# powersystem.net
KiCad netlist of a schematic drawn in EAGLE
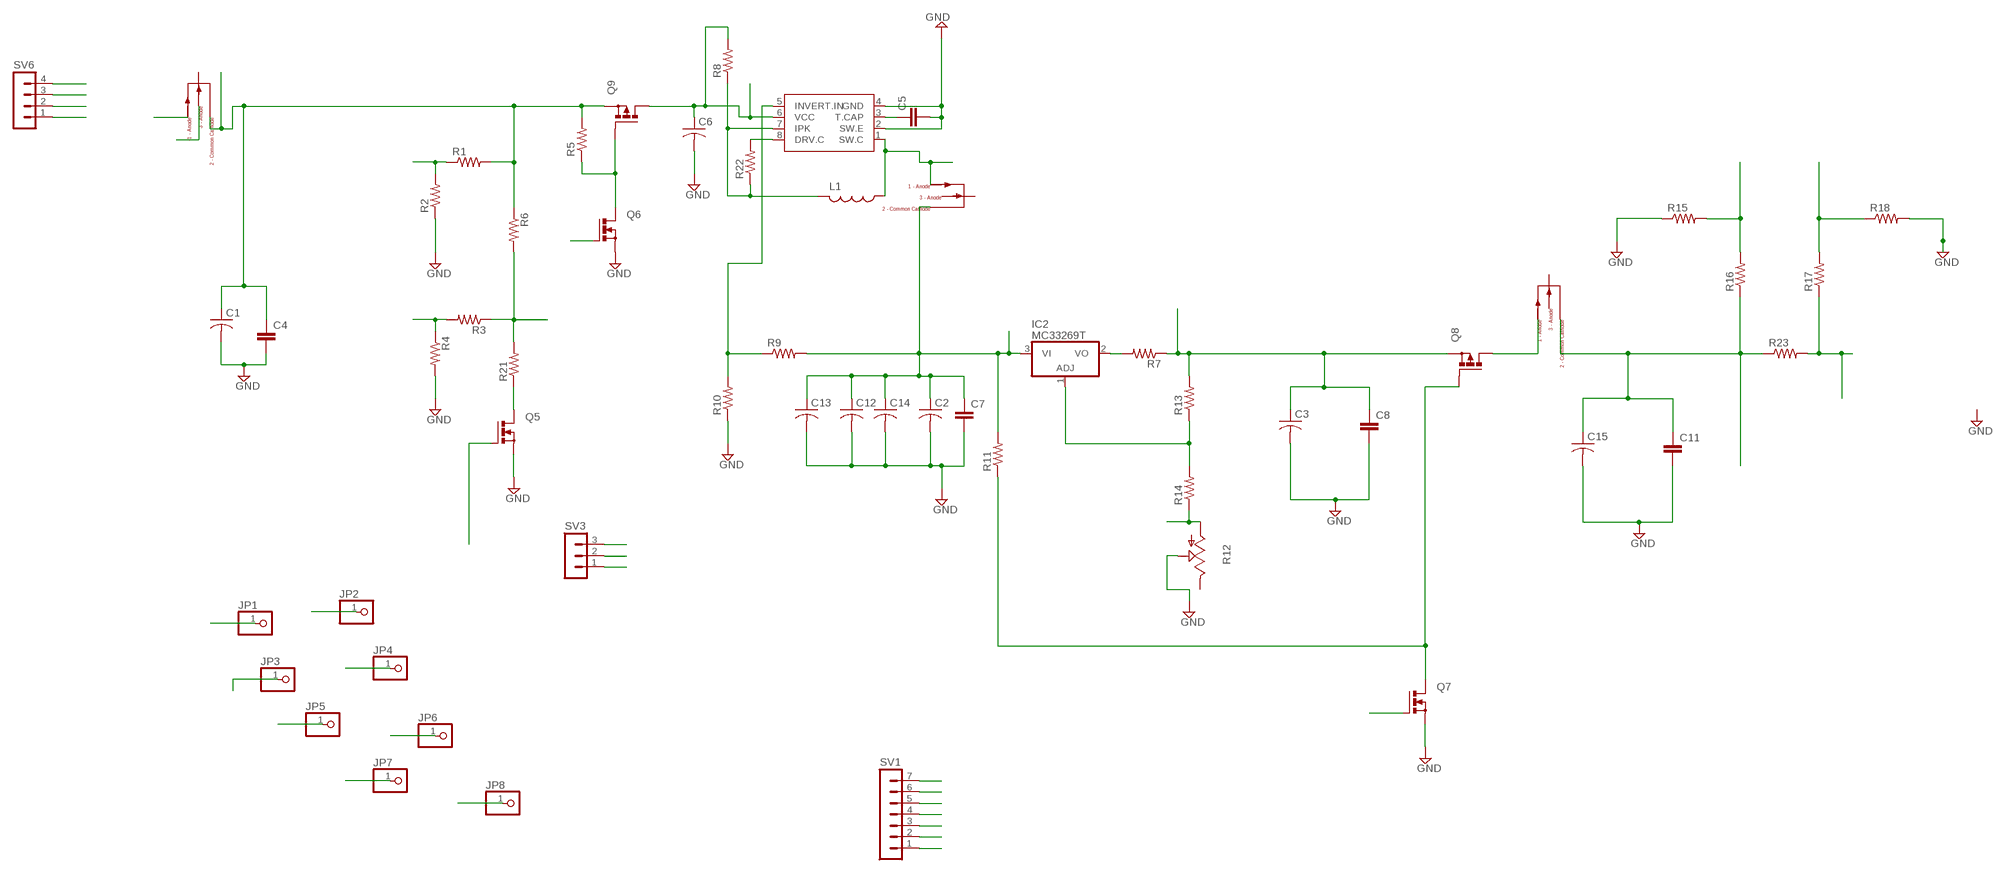
[diagram p0: schematic, sheet 1]

(export (version "E")
  (design (tool "Eeschema 10.0.6"))
  (components
    (comp (ref "C1")
      (value "C-US025-024X044")
      (footprint "eagle-import:C025-024X044")
      (libsource (lib "eagle-import") (part "C-US025-024X044"))
    )
    (comp (ref "C2")
      (value "C-US025-024X044")
      (footprint "eagle-import:C025-024X044")
      (libsource (lib "eagle-import") (part "C-US025-024X044"))
    )
    (comp (ref "C3")
      (value "C-US025-024X044")
      (footprint "eagle-import:C025-024X044")
      (libsource (lib "eagle-import") (part "C-US025-024X044"))
    )
    (comp (ref "C4")
      (value "C2.5/2")
      (footprint "eagle-import:C2.5-2")
      (libsource (lib "eagle-import") (part "C2.5/2"))
    )
    (comp (ref "C5")
      (value "C2.5/2")
      (footprint "eagle-import:C2.5-2")
      (libsource (lib "eagle-import") (part "C2.5/2"))
    )
    (comp (ref "C6")
      (value "C-US025-024X044")
      (footprint "eagle-import:C025-024X044")
      (libsource (lib "eagle-import") (part "C-US025-024X044"))
    )
    (comp (ref "C7")
      (value "C2.5/2")
      (footprint "eagle-import:C2.5-2")
      (libsource (lib "eagle-import") (part "C2.5/2"))
    )
    (comp (ref "C8")
      (value "C2.5/2")
      (footprint "eagle-import:C2.5-2")
      (libsource (lib "eagle-import") (part "C2.5/2"))
    )
    (comp (ref "C11")
      (value "C2.5/2")
      (footprint "eagle-import:C2.5-2")
      (libsource (lib "eagle-import") (part "C2.5/2"))
    )
    (comp (ref "C12")
      (value "C-US025-024X044")
      (footprint "eagle-import:C025-024X044")
      (libsource (lib "eagle-import") (part "C-US025-024X044"))
    )
    (comp (ref "C13")
      (value "C-US025-024X044")
      (footprint "eagle-import:C025-024X044")
      (libsource (lib "eagle-import") (part "C-US025-024X044"))
    )
    (comp (ref "C14")
      (value "C-US025-024X044")
      (footprint "eagle-import:C025-024X044")
      (libsource (lib "eagle-import") (part "C-US025-024X044"))
    )
    (comp (ref "C15")
      (value "C-US025-024X044")
      (footprint "eagle-import:C025-024X044")
      (libsource (lib "eagle-import") (part "C-US025-024X044"))
    )
    (comp (ref "IC2")
      (value "MC33269T")
      (footprint "eagle-import:TO220V")
      (libsource (lib "eagle-import") (part "MC33269?T"))
    )
    (comp (ref "JP1")
      (value "PINHD-1X1")
      (footprint "eagle-import:1X01")
      (libsource (lib "eagle-import") (part "PINHD-1X1"))
    )
    (comp (ref "JP2")
      (value "PINHD-1X1")
      (footprint "eagle-import:1X01")
      (libsource (lib "eagle-import") (part "PINHD-1X1"))
    )
    (comp (ref "JP3")
      (value "PINHD-1X1")
      (footprint "eagle-import:1X01")
      (libsource (lib "eagle-import") (part "PINHD-1X1"))
    )
    (comp (ref "JP4")
      (value "PINHD-1X1")
      (footprint "eagle-import:1X01")
      (libsource (lib "eagle-import") (part "PINHD-1X1"))
    )
    (comp (ref "JP5")
      (value "PINHD-1X1")
      (footprint "eagle-import:1X01")
      (libsource (lib "eagle-import") (part "PINHD-1X1"))
    )
    (comp (ref "JP6")
      (value "PINHD-1X1")
      (footprint "eagle-import:1X01")
      (libsource (lib "eagle-import") (part "PINHD-1X1"))
    )
    (comp (ref "JP7")
      (value "PINHD-1X1")
      (footprint "eagle-import:1X01")
      (libsource (lib "eagle-import") (part "PINHD-1X1"))
    )
    (comp (ref "JP8")
      (value "PINHD-1X1")
      (footprint "eagle-import:1X01")
      (libsource (lib "eagle-import") (part "PINHD-1X1"))
    )
    (comp (ref "L1")
      (value "L-US0204/5")
      (footprint "eagle-import:0204_5")
      (libsource (lib "eagle-import") (part "L-US0204/5"))
    )
    (comp (ref "Q1")
      (value "PMOSFET_N")
      (footprint "eagle-import:TO220BV")
      (libsource (lib "eagle-import") (part "PMOSFET_N"))
    )
    (comp (ref "Q2")
      (value "PMOSFET_N")
      (footprint "eagle-import:TO220BV")
      (libsource (lib "eagle-import") (part "PMOSFET_N"))
    )
    (comp (ref "Q3")
      (value "PMOSFET_N")
      (footprint "eagle-import:TO220BV")
      (libsource (lib "eagle-import") (part "PMOSFET_N"))
    )
    (comp (ref "Q4")
      (value "UCC38050")
      (footprint "eagle-import:DIP-8")
      (libsource (lib "eagle-import") (part "UCC38050"))
    )
    (comp (ref "Q5")
      (value "PMOSFET_NTO220BV")
      (footprint "eagle-import:TO220BV")
      (libsource (lib "eagle-import") (part "transistor-power_400_PMOSFET_NTO220BV"))
    )
    (comp (ref "Q6")
      (value "PMOSFET_NTO220BV")
      (footprint "eagle-import:TO220BV")
      (libsource (lib "eagle-import") (part "transistor-power_400_PMOSFET_NTO220BV"))
    )
    (comp (ref "Q7")
      (value "PMOSFET_NTO220BV")
      (footprint "eagle-import:TO220BV")
      (libsource (lib "eagle-import") (part "transistor-power_400_PMOSFET_NTO220BV"))
    )
    (comp (ref "Q8")
      (value "PMOSFET_PTO220BV")
      (footprint "eagle-import:TO220BV")
      (libsource (lib "eagle-import") (part "PMOSFET_PTO220BV"))
    )
    (comp (ref "Q9")
      (value "PMOSFET_PTO220BV")
      (footprint "eagle-import:TO220BV")
      (libsource (lib "eagle-import") (part "PMOSFET_PTO220BV"))
    )
    (comp (ref "R1")
      (value "R-US_0204/7")
      (footprint "eagle-import:0204_7")
      (libsource (lib "eagle-import") (part "resistor_348_R-US_0204/7"))
    )
    (comp (ref "R2")
      (value "R-US_0204/7")
      (footprint "eagle-import:0204_7")
      (libsource (lib "eagle-import") (part "resistor_348_R-US_0204/7"))
    )
    (comp (ref "R3")
      (value "R-US_0204/7")
      (footprint "eagle-import:0204_7")
      (libsource (lib "eagle-import") (part "resistor_348_R-US_0204/7"))
    )
    (comp (ref "R4")
      (value "R-US_0204/7")
      (footprint "eagle-import:0204_7")
      (libsource (lib "eagle-import") (part "resistor_348_R-US_0204/7"))
    )
    (comp (ref "R5")
      (value "R-US_0204/7")
      (footprint "eagle-import:0204_7")
      (libsource (lib "eagle-import") (part "resistor_348_R-US_0204/7"))
    )
    (comp (ref "R6")
      (value "R-US_0204/7")
      (footprint "eagle-import:0204_7")
      (libsource (lib "eagle-import") (part "resistor_348_R-US_0204/7"))
    )
    (comp (ref "R7")
      (value "R-US_0207/10")
      (footprint "eagle-import:0207_10")
      (libsource (lib "eagle-import") (part "R-US_0207/10"))
    )
    (comp (ref "R8")
      (value "R-US_0207/10")
      (footprint "eagle-import:0207_10")
      (libsource (lib "eagle-import") (part "R-US_0207/10"))
    )
    (comp (ref "R9")
      (value "R-US_0204/7")
      (footprint "eagle-import:0204_7")
      (libsource (lib "eagle-import") (part "resistor_348_R-US_0204/7"))
    )
    (comp (ref "R10")
      (value "R-US_0204/7")
      (footprint "eagle-import:0204_7")
      (libsource (lib "eagle-import") (part "resistor_348_R-US_0204/7"))
    )
    (comp (ref "R11")
      (value "R-US_0204/7")
      (footprint "eagle-import:0204_7")
      (libsource (lib "eagle-import") (part "resistor_348_R-US_0204/7"))
    )
    (comp (ref "R12")
      (value "TRIM_US-CA6H")
      (footprint "eagle-import:CA6H")
      (libsource (lib "eagle-import") (part "TRIM_US-CA6H"))
    )
    (comp (ref "R13")
      (value "R-US_0204/7")
      (footprint "eagle-import:0204_7")
      (libsource (lib "eagle-import") (part "resistor_348_R-US_0204/7"))
    )
    (comp (ref "R14")
      (value "R-US_0204/7")
      (footprint "eagle-import:0204_7")
      (libsource (lib "eagle-import") (part "resistor_348_R-US_0204/7"))
    )
    (comp (ref "R15")
      (value "R-US_0204/7")
      (footprint "eagle-import:0204_7")
      (libsource (lib "eagle-import") (part "resistor_348_R-US_0204/7"))
    )
    (comp (ref "R16")
      (value "R-US_0204/7")
      (footprint "eagle-import:0204_7")
      (libsource (lib "eagle-import") (part "resistor_348_R-US_0204/7"))
    )
    (comp (ref "R17")
      (value "R-US_0204/7")
      (footprint "eagle-import:0204_7")
      (libsource (lib "eagle-import") (part "R-US_0204/7"))
    )
    (comp (ref "R18")
      (value "R-US_0204/7")
      (footprint "eagle-import:0204_7")
      (libsource (lib "eagle-import") (part "R-US_0204/7"))
    )
    (comp (ref "R21")
      (value "R-US_0204/7")
      (footprint "eagle-import:0204_7")
      (libsource (lib "eagle-import") (part "resistor_348_R-US_0204/7"))
    )
    (comp (ref "R22")
      (value "R-US_0207/10")
      (footprint "eagle-import:0207_10")
      (libsource (lib "eagle-import") (part "R-US_0207/10"))
    )
    (comp (ref "R23")
      (value "R-US_0207/10")
      (footprint "eagle-import:0207_10")
      (libsource (lib "eagle-import") (part "R-US_0207/10"))
    )
    (comp (ref "SV1")
      (value "MA07-1")
      (footprint "eagle-import:MA07-1")
      (libsource (lib "eagle-import") (part "MA07-1"))
    )
    (comp (ref "SV3")
      (value "MA03-1")
      (footprint "eagle-import:MA03-1")
      (libsource (lib "eagle-import") (part "MA03-1"))
    )
    (comp (ref "SV6")
      (value "MA04-1")
      (footprint "eagle-import:MA04-1")
      (libsource (lib "eagle-import") (part "MA04-1"))
    )
  )
  (nets
    (net (code "1") (name "/BATTERY") (class "Default")
      (node (ref "JP8") (pin "1") (pinfunction "1_1") (pintype "passive"))
      (node (ref "R17") (pin "1") (pinfunction "1_1") (pintype "passive"))
      (node (ref "R23") (pin "2") (pinfunction "2_2") (pintype "passive"))
      (node (ref "SV1") (pin "3") (pinfunction "3_3") (pintype "passive"))
    )
    (net (code "2") (name "/BATTERYLEFT") (class "Default")
      (node (ref "R15") (pin "2") (pinfunction "2_2") (pintype "passive"))
      (node (ref "R16") (pin "2") (pinfunction "2_2") (pintype "passive"))
      (node (ref "SV6") (pin "3") (pinfunction "3_3") (pintype "passive"))
    )
    (net (code "3") (name "/BATTERYRIGHT") (class "Default")
      (node (ref "R17") (pin "2") (pinfunction "2_2") (pintype "passive"))
      (node (ref "R18") (pin "1") (pinfunction "1_1") (pintype "passive"))
      (node (ref "SV6") (pin "4") (pinfunction "4_4") (pintype "passive"))
    )
    (net (code "4") (name "/BETWEENRESISTOR") (class "Default")
      (node (ref "JP2") (pin "1") (pinfunction "1_1") (pintype "passive"))
      (node (ref "R21") (pin "2") (pinfunction "2_2") (pintype "passive"))
      (node (ref "R3") (pin "1") (pinfunction "1_1") (pintype "passive"))
      (node (ref "R6") (pin "2") (pinfunction "2_2") (pintype "passive"))
    )
    (net (code "5") (name "/DIODE1") (class "Default")
      (node (ref "C1") (pin "1") (pinfunction "1_1") (pintype "passive"))
      (node (ref "C4") (pin "1") (pinfunction "1_1") (pintype "passive"))
      (node (ref "JP1") (pin "1") (pinfunction "1_1") (pintype "passive"))
      (node (ref "Q1") (pin "D") (pinfunction "D_D") (pintype "passive"))
      (node (ref "Q9") (pin "S") (pinfunction "S_S") (pintype "passive"))
      (node (ref "R1") (pin "2") (pinfunction "2_2") (pintype "passive"))
      (node (ref "R5") (pin "2") (pinfunction "2_2") (pintype "passive"))
      (node (ref "R6") (pin "1") (pinfunction "1_1") (pintype "passive"))
    )
    (net (code "6") (name "/DUMMYLOADBOTTOM") (class "Default")
      (node (ref "R3") (pin "2") (pinfunction "2_2") (pintype "passive"))
      (node (ref "R4") (pin "1") (pinfunction "1_1") (pintype "passive"))
      (node (ref "SV6") (pin "2") (pinfunction "2_2") (pintype "passive"))
    )
    (net (code "7") (name "/DUMMYLOADSWITCH") (class "Default")
      (node (ref "Q5") (pin "G") (pinfunction "G_G") (pintype "passive"))
      (node (ref "SV3") (pin "1") (pinfunction "1_1") (pintype "passive"))
    )
    (net (code "8") (name "/DUMMYLOADTOP") (class "Default")
      (node (ref "R1") (pin "1") (pinfunction "1_1") (pintype "passive"))
      (node (ref "R2") (pin "2") (pinfunction "2_2") (pintype "passive"))
      (node (ref "SV6") (pin "1") (pinfunction "1_1") (pintype "passive"))
    )
    (net (code "9") (name "/LOAD") (class "Default")
      (node (ref "C11") (pin "1") (pinfunction "1_1") (pintype "passive"))
      (node (ref "C15") (pin "1") (pinfunction "1_1") (pintype "passive"))
      (node (ref "Q3") (pin "D") (pinfunction "D_D") (pintype "passive"))
      (node (ref "R16") (pin "1") (pinfunction "1_1") (pintype "passive"))
      (node (ref "R23") (pin "1") (pinfunction "1_1") (pintype "passive"))
      (node (ref "SV1") (pin "4") (pinfunction "4_4") (pintype "passive"))
    )
    (net (code "10") (name "/PINOUT1") (class "Default")
      (node (ref "JP4") (pin "1") (pinfunction "1_1") (pintype "passive"))
      (node (ref "L1") (pin "1") (pinfunction "1_1") (pintype "passive"))
      (node (ref "Q2") (pin "S") (pinfunction "S_S") (pintype "passive"))
      (node (ref "Q4") (pin "1") (pinfunction "SW.C_1") (pintype "input"))
    )
    (net (code "11") (name "/PINOUT6") (class "Default")
      (node (ref "C6") (pin "1") (pinfunction "1_1") (pintype "passive"))
      (node (ref "JP3") (pin "1") (pinfunction "1_1") (pintype "passive"))
      (node (ref "Q4") (pin "6") (pinfunction "VCC_6") (pintype "power_in"))
      (node (ref "Q9") (pin "D") (pinfunction "D_D") (pintype "passive"))
      (node (ref "R8") (pin "2") (pinfunction "2_2") (pintype "passive"))
    )
    (net (code "12") (name "/POT") (class "Default")
      (node (ref "JP7") (pin "1") (pinfunction "1_1") (pintype "passive"))
      (node (ref "R12") (pin "A") (pinfunction "A_A") (pintype "passive"))
      (node (ref "R14") (pin "1") (pinfunction "1_1") (pintype "passive"))
    )
    (net (code "13") (name "/PRIMARYNOSUNLIGHT") (class "Default")
      (node (ref "Q6") (pin "G") (pinfunction "G_G") (pintype "passive"))
      (node (ref "SV3") (pin "2") (pinfunction "2_2") (pintype "passive"))
    )
    (net (code "14") (name "/SECONDARYNOSUNLIGHT") (class "Default")
      (node (ref "Q7") (pin "G") (pinfunction "G_G") (pintype "passive"))
      (node (ref "SV3") (pin "3") (pinfunction "3_3") (pintype "passive"))
    )
    (net (code "15") (name "/SOLARPANEL1") (class "Default")
      (node (ref "Q1") (pin "S") (pinfunction "S_S") (pintype "passive"))
      (node (ref "SV1") (pin "1") (pinfunction "1_1") (pintype "passive"))
    )
    (net (code "16") (name "/SOLARPANEL2") (class "Default")
      (node (ref "Q1") (pin "G") (pinfunction "G_G") (pintype "passive"))
      (node (ref "SV1") (pin "2") (pinfunction "2_2") (pintype "passive"))
    )
    (net (code "17") (name "/VINREG") (class "Default")
      (node (ref "C12") (pin "1") (pinfunction "1_1") (pintype "passive"))
      (node (ref "C13") (pin "1") (pinfunction "1_1") (pintype "passive"))
      (node (ref "C14") (pin "1") (pinfunction "1_1") (pintype "passive"))
      (node (ref "C2") (pin "1") (pinfunction "1_1") (pintype "passive"))
      (node (ref "C7") (pin "1") (pinfunction "1_1") (pintype "passive"))
      (node (ref "IC2") (pin "3") (pinfunction "VI_3") (pintype "input"))
      (node (ref "JP5") (pin "1") (pinfunction "1_1") (pintype "passive"))
      (node (ref "Q2") (pin "D") (pinfunction "D_D") (pintype "passive"))
      (node (ref "R11") (pin "2") (pinfunction "2_2") (pintype "passive"))
      (node (ref "R9") (pin "2") (pinfunction "2_2") (pintype "passive"))
    )
    (net (code "18") (name "/VOUTREG") (class "Default")
      (node (ref "C3") (pin "1") (pinfunction "1_1") (pintype "passive"))
      (node (ref "C8") (pin "1") (pinfunction "1_1") (pintype "passive"))
      (node (ref "JP6") (pin "1") (pinfunction "1_1") (pintype "passive"))
      (node (ref "Q8") (pin "S") (pinfunction "S_S") (pintype "passive"))
      (node (ref "R13") (pin "2") (pinfunction "2_2") (pintype "passive"))
      (node (ref "R7") (pin "1") (pinfunction "1_1") (pintype "passive"))
    )
    (net (code "19") (name "GND") (class "Default")
      (node (ref "C1") (pin "2") (pinfunction "2_2") (pintype "passive"))
      (node (ref "C11") (pin "2") (pinfunction "2_2") (pintype "passive"))
      (node (ref "C12") (pin "2") (pinfunction "2_2") (pintype "passive"))
      (node (ref "C13") (pin "2") (pinfunction "2_2") (pintype "passive"))
      (node (ref "C14") (pin "2") (pinfunction "2_2") (pintype "passive"))
      (node (ref "C15") (pin "2") (pinfunction "2_2") (pintype "passive"))
      (node (ref "C2") (pin "2") (pinfunction "2_2") (pintype "passive"))
      (node (ref "C3") (pin "2") (pinfunction "2_2") (pintype "passive"))
      (node (ref "C4") (pin "2") (pinfunction "2_2") (pintype "passive"))
      (node (ref "C5") (pin "2") (pinfunction "2_2") (pintype "passive"))
      (node (ref "C6") (pin "2") (pinfunction "2_2") (pintype "passive"))
      (node (ref "C7") (pin "2") (pinfunction "2_2") (pintype "passive"))
      (node (ref "C8") (pin "2") (pinfunction "2_2") (pintype "passive"))
      (node (ref "Q4") (pin "2") (pinfunction "SW.E_2") (pintype "output"))
      (node (ref "Q4") (pin "4") (pinfunction "GND_4") (pintype "input"))
      (node (ref "Q5") (pin "S") (pinfunction "S_S") (pintype "passive"))
      (node (ref "Q6") (pin "S") (pinfunction "S_S") (pintype "passive"))
      (node (ref "Q7") (pin "S") (pinfunction "S_S") (pintype "passive"))
      (node (ref "R10") (pin "1") (pinfunction "1_1") (pintype "passive"))
      (node (ref "R12") (pin "S") (pinfunction "S_S") (pintype "passive"))
      (node (ref "R15") (pin "1") (pinfunction "1_1") (pintype "passive"))
      (node (ref "R18") (pin "2") (pinfunction "2_2") (pintype "passive"))
      (node (ref "R2") (pin "1") (pinfunction "1_1") (pintype "passive"))
      (node (ref "R4") (pin "2") (pinfunction "2_2") (pintype "passive"))
      (node (ref "SV1") (pin "5") (pinfunction "5_5") (pintype "passive"))
      (node (ref "SV1") (pin "6") (pinfunction "6_6") (pintype "passive"))
      (node (ref "SV1") (pin "7") (pinfunction "7_7") (pintype "passive"))
    )
    (net (code "20") (name "Net-(IC2-ADJ)") (class "Default")
      (node (ref "IC2") (pin "1") (pinfunction "ADJ_1") (pintype "input"))
      (node (ref "R13") (pin "1") (pinfunction "1_1") (pintype "passive"))
      (node (ref "R14") (pin "2") (pinfunction "2_2") (pintype "passive"))
    )
    (net (code "21") (name "Net-(IC2-VO)") (class "Default")
      (node (ref "IC2") (pin "2") (pinfunction "VO_2") (pintype "passive"))
      (node (ref "R7") (pin "2") (pinfunction "2_2") (pintype "passive"))
    )
    (net (code "22") (name "Net-(Q3-PadS)") (class "Default")
      (node (ref "Q3") (pin "S") (pinfunction "S_S") (pintype "passive"))
      (node (ref "Q8") (pin "D") (pinfunction "D_D") (pintype "passive"))
    )
    (net (code "23") (name "Net-(Q4-DRV.C)") (class "Default")
      (node (ref "Q4") (pin "8") (pinfunction "DRV.C_8") (pintype "power_in"))
      (node (ref "R22") (pin "2") (pinfunction "2_2") (pintype "passive"))
    )
    (net (code "24") (name "Net-(Q4-INVERT.IN)") (class "Default")
      (node (ref "Q4") (pin "5") (pinfunction "INVERT.IN_5") (pintype "input"))
      (node (ref "R10") (pin "2") (pinfunction "2_2") (pintype "passive"))
      (node (ref "R9") (pin "1") (pinfunction "1_1") (pintype "passive"))
    )
    (net (code "25") (name "Net-(Q4-IPK)") (class "Default")
      (node (ref "L1") (pin "2") (pinfunction "2_2") (pintype "passive"))
      (node (ref "Q4") (pin "7") (pinfunction "IPK_7") (pintype "output"))
      (node (ref "R22") (pin "1") (pinfunction "1_1") (pintype "passive"))
      (node (ref "R8") (pin "1") (pinfunction "1_1") (pintype "passive"))
    )
    (net (code "26") (name "Net-(Q4-T.CAP)") (class "Default")
      (node (ref "C5") (pin "1") (pinfunction "1_1") (pintype "passive"))
      (node (ref "Q4") (pin "3") (pinfunction "T.CAP_3") (pintype "input"))
    )
    (net (code "27") (name "Net-(Q5-PadD)") (class "Default")
      (node (ref "Q5") (pin "D") (pinfunction "D_D") (pintype "passive"))
      (node (ref "R21") (pin "1") (pinfunction "1_1") (pintype "passive"))
    )
    (net (code "28") (name "Net-(Q6-PadD)") (class "Default")
      (node (ref "Q6") (pin "D") (pinfunction "D_D") (pintype "passive"))
      (node (ref "Q9") (pin "G") (pinfunction "G_G") (pintype "passive"))
      (node (ref "R5") (pin "1") (pinfunction "1_1") (pintype "passive"))
    )
    (net (code "29") (name "Net-(Q7-PadD)") (class "Default")
      (node (ref "Q7") (pin "D") (pinfunction "D_D") (pintype "passive"))
      (node (ref "Q8") (pin "G") (pinfunction "G_G") (pintype "passive"))
      (node (ref "R11") (pin "1") (pinfunction "1_1") (pintype "passive"))
    )
    (net (code "30") (name "unconnected-(Q2-PadG)") (class "Default")
      (node (ref "Q2") (pin "G") (pinfunction "G_G") (pintype "passive"))
    )
    (net (code "31") (name "unconnected-(Q3-PadG)") (class "Default")
      (node (ref "Q3") (pin "G") (pinfunction "G_G") (pintype "passive"))
    )
    (net (code "32") (name "unconnected-(R12-PadE)") (class "Default")
      (node (ref "R12") (pin "E") (pinfunction "E_E") (pintype "passive"))
    )
  )
)
